# untitled.net
KiCad netlist of a schematic drawn in EAGLE
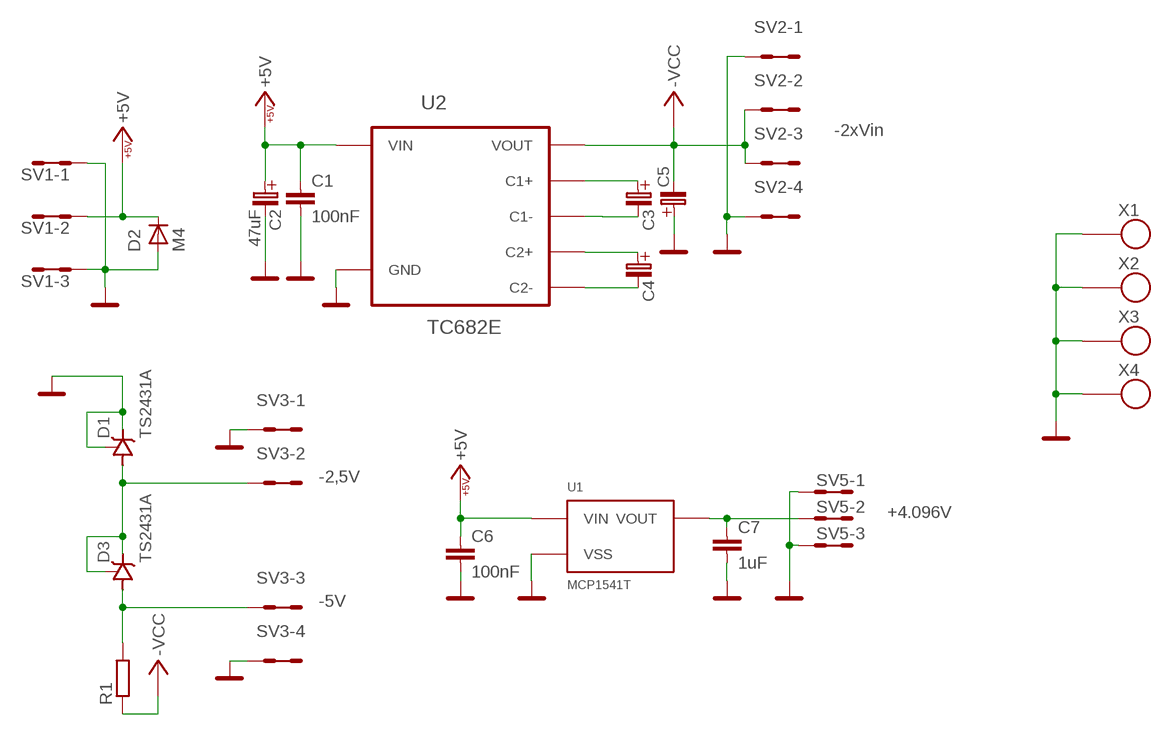
[diagram p0: schematic, sheet 1]

(export (version "E")
  (design (tool "Eeschema 10.0.6"))
  (components
    (comp (ref "C1")
      (value "100nF")
      (footprint "eagle-import:C0805")
      (libsource (lib "eagle-import") (part "C0805"))
    )
    (comp (ref "C2") (value "47uF") (footprint "eagle-import:C") (libsource (lib "eagle-import") (part "C")))
    (comp (ref "C3") (value "C") (footprint "eagle-import:C") (libsource (lib "eagle-import") (part "C")))
    (comp (ref "C4") (value "C") (footprint "eagle-import:C") (libsource (lib "eagle-import") (part "C")))
    (comp (ref "C5") (value "C") (footprint "eagle-import:C") (libsource (lib "eagle-import") (part "C")))
    (comp (ref "C6")
      (value "100nF")
      (footprint "eagle-import:C0805")
      (libsource (lib "eagle-import") (part "C0805"))
    )
    (comp (ref "C7")
      (value "1uF")
      (footprint "eagle-import:C0805")
      (libsource (lib "eagle-import") (part "C0805"))
    )
    (comp (ref "D1")
      (value "TS2431A")
      (footprint "eagle-import:SOT23")
      (libsource (lib "eagle-import") (part "TS2431A"))
    )
    (comp (ref "D2")
      (value "M4")
      (footprint "eagle-import:SMA")
      (libsource (lib "eagle-import") (part "D-OB.SMA"))
    )
    (comp (ref "D3")
      (value "TS2431A")
      (footprint "eagle-import:SOT23")
      (libsource (lib "eagle-import") (part "TS2431A"))
    )
    (comp (ref "R1")
      (value "R0805")
      (footprint "eagle-import:0805")
      (libsource (lib "eagle-import") (part "R0805"))
    )
    (comp (ref "SV1")
      (value "MA03-2")
      (footprint "eagle-import:MA03-2")
      (libsource (lib "eagle-import") (part "MA03-2"))
    )
    (comp (ref "SV2")
      (value "MA04-2")
      (footprint "eagle-import:MA04-2")
      (libsource (lib "eagle-import") (part "MA04-2"))
    )
    (comp (ref "SV3")
      (value "MA04-2")
      (footprint "eagle-import:MA04-2")
      (libsource (lib "eagle-import") (part "MA04-2"))
    )
    (comp (ref "SV5")
      (value "MA03-2")
      (footprint "eagle-import:MA03-2")
      (libsource (lib "eagle-import") (part "MA03-2"))
    )
    (comp (ref "U1")
      (value "MCP1541T")
      (footprint "eagle-import:SOT23")
      (libsource (lib "eagle-import") (part "MCP1541T"))
    )
    (comp (ref "U2")
      (value "TC682E")
      (footprint "eagle-import:SO8")
      (libsource (lib "eagle-import") (part "TC682"))
    )
    (comp (ref "X1")
      (value "SROUB3M")
      (footprint "eagle-import:SROUB3M")
      (libsource (lib "eagle-import") (part "SROUB3M"))
    )
    (comp (ref "X2")
      (value "SROUB3M")
      (footprint "eagle-import:SROUB3M")
      (libsource (lib "eagle-import") (part "SROUB3M"))
    )
    (comp (ref "X3")
      (value "SROUB3M")
      (footprint "eagle-import:SROUB3M")
      (libsource (lib "eagle-import") (part "SROUB3M"))
    )
    (comp (ref "X4")
      (value "SROUB3M")
      (footprint "eagle-import:SROUB3M")
      (libsource (lib "eagle-import") (part "SROUB3M"))
    )
  )
  (nets
    (net (code "1") (name "+5V") (class "Default")
      (node (ref "C1") (pin "1") (pinfunction "1_1") (pintype "passive"))
      (node (ref "C2") (pin "+") (pinfunction "C_EL+_+") (pintype "passive"))
      (node (ref "C6") (pin "1") (pinfunction "1_1") (pintype "passive"))
      (node (ref "D2") (pin "K") (pinfunction "C_K") (pintype "passive"))
      (node (ref "SV1") (pin "3") (pinfunction "K_3") (pintype "passive"))
      (node (ref "SV1") (pin "4") (pinfunction "K_4") (pintype "passive"))
      (node (ref "U1") (pin "1") (pinfunction "VIN_1") (pintype "bidirectional"))
      (node (ref "U2") (pin "6") (pinfunction "VIN_6") (pintype "bidirectional"))
    )
    (net (code "2") (name "-VCC") (class "Default")
      (node (ref "C5") (pin "-") (pinfunction "C_EL-_-") (pintype "passive"))
      (node (ref "R1") (pin "1") (pinfunction "1_1") (pintype "passive"))
      (node (ref "SV2") (pin "3") (pinfunction "K_3") (pintype "passive"))
      (node (ref "SV2") (pin "4") (pinfunction "K_4") (pintype "passive"))
      (node (ref "SV2") (pin "5") (pinfunction "K_5") (pintype "passive"))
      (node (ref "SV2") (pin "6") (pinfunction "K_6") (pintype "passive"))
      (node (ref "U2") (pin "4") (pinfunction "VOUT_4") (pintype "bidirectional"))
    )
    (net (code "3") (name "GND") (class "Default")
      (node (ref "C1") (pin "2") (pinfunction "2_2") (pintype "passive"))
      (node (ref "C2") (pin "-") (pinfunction "C_EL-_-") (pintype "passive"))
      (node (ref "C5") (pin "+") (pinfunction "C_EL+_+") (pintype "passive"))
      (node (ref "C6") (pin "2") (pinfunction "2_2") (pintype "passive"))
      (node (ref "C7") (pin "2") (pinfunction "2_2") (pintype "passive"))
      (node (ref "D1") (pin "1") (pinfunction "K_1") (pintype "passive"))
      (node (ref "D1") (pin "2") (pinfunction "P$1_2") (pintype "passive"))
      (node (ref "D2") (pin "A") (pinfunction "A_A") (pintype "passive"))
      (node (ref "SV1") (pin "1") (pinfunction "K_1") (pintype "passive"))
      (node (ref "SV1") (pin "2") (pinfunction "K_2") (pintype "passive"))
      (node (ref "SV1") (pin "5") (pinfunction "K_5") (pintype "passive"))
      (node (ref "SV1") (pin "6") (pinfunction "K_6") (pintype "passive"))
      (node (ref "SV2") (pin "1") (pinfunction "K_1") (pintype "passive"))
      (node (ref "SV2") (pin "2") (pinfunction "K_2") (pintype "passive"))
      (node (ref "SV2") (pin "7") (pinfunction "K_7") (pintype "passive"))
      (node (ref "SV2") (pin "8") (pinfunction "K_8") (pintype "passive"))
      (node (ref "SV3") (pin "1") (pinfunction "K_1") (pintype "passive"))
      (node (ref "SV3") (pin "2") (pinfunction "K_2") (pintype "passive"))
      (node (ref "SV3") (pin "7") (pinfunction "K_7") (pintype "passive"))
      (node (ref "SV3") (pin "8") (pinfunction "K_8") (pintype "passive"))
      (node (ref "SV5") (pin "1") (pinfunction "K_1") (pintype "passive"))
      (node (ref "SV5") (pin "2") (pinfunction "K_2") (pintype "passive"))
      (node (ref "SV5") (pin "5") (pinfunction "K_5") (pintype "passive"))
      (node (ref "SV5") (pin "6") (pinfunction "K_6") (pintype "passive"))
      (node (ref "U1") (pin "3") (pinfunction "VSS_3") (pintype "bidirectional"))
      (node (ref "U2") (pin "5") (pinfunction "GND_5") (pintype "bidirectional"))
      (node (ref "X1") (pin "P$1") (pinfunction "P$1_P$1") (pintype "bidirectional"))
      (node (ref "X2") (pin "P$1") (pinfunction "P$1_P$1") (pintype "bidirectional"))
      (node (ref "X3") (pin "P$1") (pinfunction "P$1_P$1") (pintype "bidirectional"))
      (node (ref "X4") (pin "P$1") (pinfunction "P$1_P$1") (pintype "bidirectional"))
    )
    (net (code "4") (name "Net-(C3-C_EL+)") (class "Default")
      (node (ref "C3") (pin "+") (pinfunction "C_EL+_+") (pintype "passive"))
      (node (ref "U2") (pin "7") (pinfunction "C1+_7") (pintype "bidirectional"))
    )
    (net (code "5") (name "Net-(C3-C_EL-)") (class "Default")
      (node (ref "C3") (pin "-") (pinfunction "C_EL-_-") (pintype "passive"))
      (node (ref "U2") (pin "1") (pinfunction "C1-_1") (pintype "bidirectional"))
    )
    (net (code "6") (name "Net-(C4-C_EL+)") (class "Default")
      (node (ref "C4") (pin "+") (pinfunction "C_EL+_+") (pintype "passive"))
      (node (ref "U2") (pin "2") (pinfunction "C2+_2") (pintype "bidirectional"))
    )
    (net (code "7") (name "Net-(C4-C_EL-)") (class "Default")
      (node (ref "C4") (pin "-") (pinfunction "C_EL-_-") (pintype "passive"))
      (node (ref "U2") (pin "3") (pinfunction "C2-_3") (pintype "bidirectional"))
    )
    (net (code "8") (name "Net-(D1-A)") (class "Default")
      (node (ref "D1") (pin "3") (pinfunction "A_3") (pintype "passive"))
      (node (ref "D3") (pin "1") (pinfunction "K_1") (pintype "passive"))
      (node (ref "D3") (pin "2") (pinfunction "P$1_2") (pintype "passive"))
      (node (ref "SV3") (pin "3") (pinfunction "K_3") (pintype "passive"))
      (node (ref "SV3") (pin "4") (pinfunction "K_4") (pintype "passive"))
    )
    (net (code "9") (name "Net-(D3-A)") (class "Default")
      (node (ref "D3") (pin "3") (pinfunction "A_3") (pintype "passive"))
      (node (ref "R1") (pin "2") (pinfunction "2_2") (pintype "passive"))
      (node (ref "SV3") (pin "5") (pinfunction "K_5") (pintype "passive"))
      (node (ref "SV3") (pin "6") (pinfunction "K_6") (pintype "passive"))
    )
    (net (code "10") (name "Net-(U1-VOUT)") (class "Default")
      (node (ref "C7") (pin "1") (pinfunction "1_1") (pintype "passive"))
      (node (ref "SV5") (pin "3") (pinfunction "K_3") (pintype "passive"))
      (node (ref "SV5") (pin "4") (pinfunction "K_4") (pintype "passive"))
      (node (ref "U1") (pin "2") (pinfunction "VOUT_2") (pintype "bidirectional"))
    )
  )
)
